# carte_ascenseur_v2.net
KiCad netlist of a schematic drawn in EAGLE
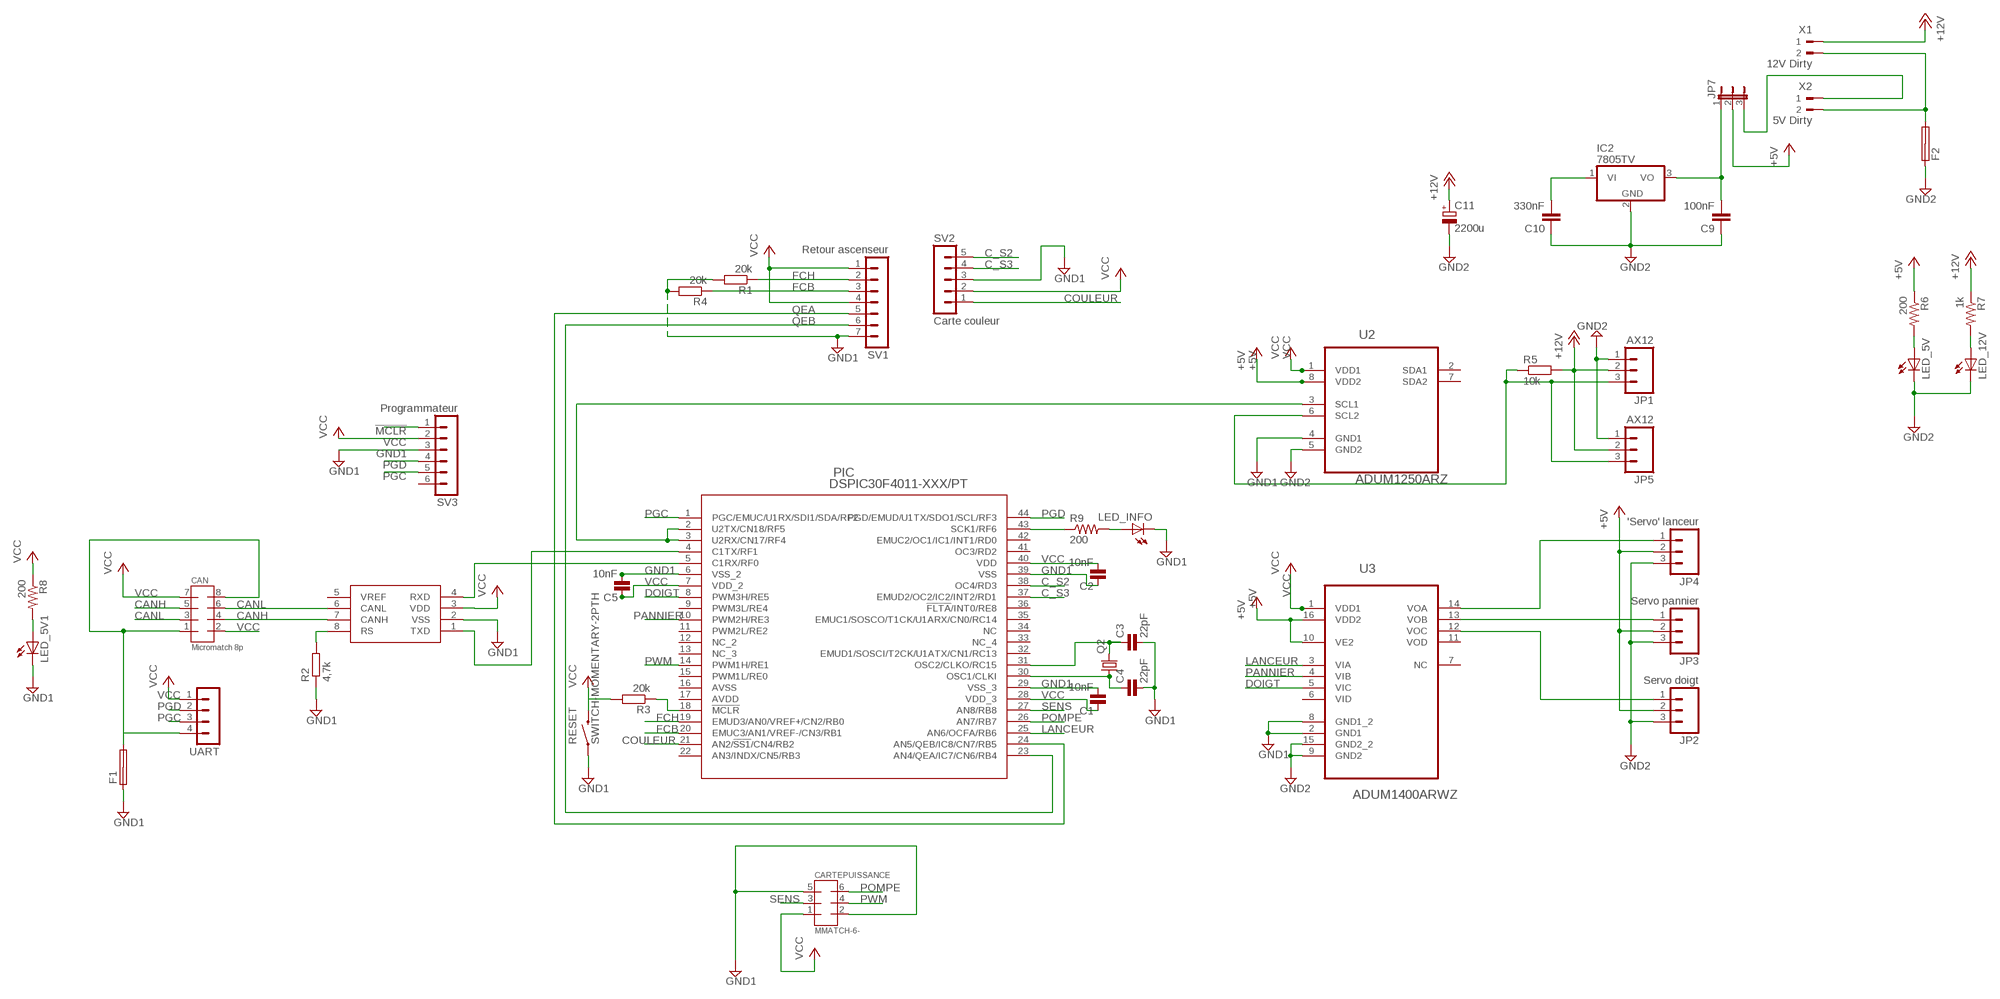
[diagram p0: schematic, sheet 1]

(export (version "E")
  (design (tool "Eeschema 10.0.6"))
  (components
    (comp (ref "C1")
      (value "10nF")
      (footprint "eagle-import:0805")
      (libsource (lib "eagle-import") (part "C0805"))
    )
    (comp (ref "C2")
      (value "10nF")
      (footprint "eagle-import:0805")
      (libsource (lib "eagle-import") (part "C0805"))
    )
    (comp (ref "C3")
      (value "22pF")
      (footprint "eagle-import:0805")
      (libsource (lib "eagle-import") (part "C0805"))
    )
    (comp (ref "C4")
      (value "22pF")
      (footprint "eagle-import:0805")
      (libsource (lib "eagle-import") (part "C0805"))
    )
    (comp (ref "C5")
      (value "10nF")
      (footprint "eagle-import:0805")
      (libsource (lib "eagle-import") (part "C0805"))
    )
    (comp (ref "C9")
      (value "100nF")
      (footprint "eagle-import:C0805")
      (libsource (lib "eagle-import") (part "C-EUC0805"))
    )
    (comp (ref "C10")
      (value "330nF")
      (footprint "eagle-import:C0805")
      (libsource (lib "eagle-import") (part "C-EUC0805"))
    )
    (comp (ref "C11")
      (value "2200u")
      (footprint "eagle-import:TT5D11")
      (libsource (lib "eagle-import") (part "CPOL-EUTT5D11"))
    )
    (comp (ref "CAN")
      (value "Micromatch 8p")
      (footprint "eagle-import:AMP-215079-8")
      (libsource (lib "eagle-import") (part "MMATCH-8-PTH"))
    )
    (comp (ref "CARTEPUISSANCE")
      (value "MMATCH-6-")
      (footprint "eagle-import:AMP-215079-6")
      (libsource (lib "eagle-import") (part "MMATCH-6-"))
    )
    (comp (ref "F1")
      (value "SHK20Q")
      (footprint "eagle-import:SHK20Q")
      (libsource (lib "eagle-import") (part "SHK20Q"))
    )
    (comp (ref "F2")
      (value "SHK20Q")
      (footprint "eagle-import:SHK20Q")
      (libsource (lib "eagle-import") (part "SHK20Q"))
    )
    (comp (ref "IC2")
      (value "7805TV")
      (footprint "eagle-import:TO220V")
      (libsource (lib "eagle-import") (part "78TV05"))
    )
    (comp (ref "JP1")
      (value "AX12")
      (footprint "eagle-import:MOLEX-1X3")
      (libsource (lib "eagle-import") (part "M03POLAR"))
    )
    (comp (ref "JP2")
      (value "Servo doigt")
      (footprint "eagle-import:1X03")
      (libsource (lib "eagle-import") (part "M03PTH"))
    )
    (comp (ref "JP3")
      (value "Servo pannier")
      (footprint "eagle-import:1X03")
      (libsource (lib "eagle-import") (part "M03PTH"))
    )
    (comp (ref "JP4")
      (value "'Servo' lanceur")
      (footprint "eagle-import:1X03")
      (libsource (lib "eagle-import") (part "M03PTH"))
    )
    (comp (ref "JP5")
      (value "AX12")
      (footprint "eagle-import:MOLEX-1X3")
      (libsource (lib "eagle-import") (part "M03POLAR"))
    )
    (comp (ref "JP7")
      (value "JP2E")
      (footprint "eagle-import:JP2")
      (libsource (lib "eagle-import") (part "JP2E"))
    )
    (comp (ref "LED_5V")
      (value "LEDCHIPLED_0805")
      (footprint "eagle-import:CHIPLED_0805")
      (libsource (lib "eagle-import") (part "LEDCHIPLED_0805"))
    )
    (comp (ref "LED_5V1")
      (value "LEDCHIPLED_0805")
      (footprint "eagle-import:CHIPLED_0805")
      (libsource (lib "eagle-import") (part "LEDCHIPLED_0805"))
    )
    (comp (ref "LED_12V")
      (value "LEDCHIPLED_0805")
      (footprint "eagle-import:CHIPLED_0805")
      (libsource (lib "eagle-import") (part "LEDCHIPLED_0805"))
    )
    (comp (ref "LED_INFO")
      (value "LEDCHIPLED_0805")
      (footprint "eagle-import:CHIPLED_0805")
      (libsource (lib "eagle-import") (part "LEDCHIPLED_0805"))
    )
    (comp (ref "PIC")
      (value "DSPIC30F4011-XXX/PT")
      (footprint "eagle-import:TQFP44_MC")
      (libsource (lib "eagle-import") (part "DSPIC30F4011-XXX/PT"))
    )
    (comp (ref "Q2")
      (value "CRYSTALHC49S")
      (footprint "eagle-import:HC49_S")
      (libsource (lib "eagle-import") (part "CRYSTALHC49S"))
    )
    (comp (ref "R1")
      (value "20k")
      (footprint "eagle-import:M0805")
      (libsource (lib "eagle-import") (part "R-EU_M0805"))
    )
    (comp (ref "R2")
      (value "4,7k")
      (footprint "eagle-import:M0805")
      (libsource (lib "eagle-import") (part "R-EU_M0805"))
    )
    (comp (ref "R3")
      (value "20k")
      (footprint "eagle-import:M0805")
      (libsource (lib "eagle-import") (part "R-EU_M0805"))
    )
    (comp (ref "R4")
      (value "20k")
      (footprint "eagle-import:M0805")
      (libsource (lib "eagle-import") (part "R-EU_M0805"))
    )
    (comp (ref "R5")
      (value "10k")
      (footprint "eagle-import:M0805")
      (libsource (lib "eagle-import") (part "R-EU_M0805"))
    )
    (comp (ref "R6")
      (value "200")
      (footprint "eagle-import:0805")
      (libsource (lib "eagle-import") (part "RESISTOR0805-RES"))
    )
    (comp (ref "R7")
      (value "1k")
      (footprint "eagle-import:0805")
      (libsource (lib "eagle-import") (part "RESISTOR0805-RES"))
    )
    (comp (ref "R8")
      (value "200")
      (footprint "eagle-import:0805")
      (libsource (lib "eagle-import") (part "RESISTOR0805-RES"))
    )
    (comp (ref "R9")
      (value "200")
      (footprint "eagle-import:0805")
      (libsource (lib "eagle-import") (part "RESISTOR0805-RES"))
    )
    (comp (ref "RESET")
      (value "SWITCH-MOMENTARY-2PTH")
      (footprint "eagle-import:TACTILE-PTH")
      (libsource (lib "eagle-import") (part "SWITCH-MOMENTARY-2PTH"))
    )
    (comp (ref "SV1")
      (value "Retour ascenseur")
      (footprint "eagle-import:MA07-1")
      (libsource (lib "eagle-import") (part "MA07-1"))
    )
    (comp (ref "SV2")
      (value "Carte couleur")
      (footprint "eagle-import:MA05-1")
      (libsource (lib "eagle-import") (part "MA05-1"))
    )
    (comp (ref "SV3")
      (value "Programmateur")
      (footprint "eagle-import:MA06-1")
      (libsource (lib "eagle-import") (part "MA06-1"))
    )
    (comp (ref "U1")
      (value "MCP2551")
      (footprint "eagle-import:SO08")
      (libsource (lib "eagle-import") (part "MCP2551"))
    )
    (comp (ref "U2")
      (value "ADUM1250ARZ")
      (footprint "eagle-import:SOIC127P600X175-8N")
      (libsource (lib "eagle-import") (part "ADUM1250ARZ"))
    )
    (comp (ref "U3")
      (value "ADUM1400ARWZ")
      (footprint "eagle-import:SOIC127P1032X265-16N")
      (libsource (lib "eagle-import") (part "ADUM1400ARWZ"))
    )
    (comp (ref "UART")
      (value "MA04-1")
      (footprint "eagle-import:MA04-1")
      (libsource (lib "eagle-import") (part "MA04-1"))
    )
    (comp (ref "X1")
      (value "12V Dirty")
      (footprint "eagle-import:90-2")
      (libsource (lib "eagle-import") (part "90-2"))
    )
    (comp (ref "X2")
      (value "5V Dirty")
      (footprint "eagle-import:90-2")
      (fields (field (name "OC_FARNELL") "unknown") (field (name "OC_NEWARK") "unknown"))
      (libsource (lib "eagle-import") (part "90-2"))
    )
  )
  (nets
    (net (code "1") (name "+5V") (class "Default")
      (node (ref "JP2") (pin "2") (pinfunction "2_2") (pintype "passive"))
      (node (ref "JP3") (pin "2") (pinfunction "2_2") (pintype "passive"))
      (node (ref "JP4") (pin "2") (pinfunction "2_2") (pintype "passive"))
      (node (ref "JP7") (pin "2") (pinfunction "2_2") (pintype "passive"))
      (node (ref "R6") (pin "1") (pinfunction "1_1") (pintype "passive"))
      (node (ref "U2") (pin "8") (pinfunction "VDD2_8") (pintype "power_in"))
      (node (ref "U3") (pin "10") (pinfunction "VE2_10") (pintype "input"))
      (node (ref "U3") (pin "16") (pinfunction "VDD2_16") (pintype "power_in"))
    )
    (net (code "2") (name "+12V") (class "Default")
      (node (ref "C11") (pin "+") (pinfunction "+_+") (pintype "passive"))
      (node (ref "JP1") (pin "2") (pinfunction "2_2") (pintype "passive"))
      (node (ref "JP5") (pin "2") (pinfunction "2_2") (pintype "passive"))
      (node (ref "R5") (pin "2") (pinfunction "2_2") (pintype "passive"))
      (node (ref "R7") (pin "1") (pinfunction "1_1") (pintype "passive"))
      (node (ref "X1") (pin "1") (pinfunction "1_1") (pintype "passive"))
    )
    (net (code "3") (name "/CANH") (class "Default")
      (node (ref "CAN") (pin "4") (pinfunction "4_4") (pintype "bidirectional"))
      (node (ref "CAN") (pin "5") (pinfunction "5_5") (pintype "bidirectional"))
      (node (ref "U1") (pin "7") (pinfunction "CANH_7") (pintype "bidirectional"))
    )
    (net (code "4") (name "/CANL") (class "Default")
      (node (ref "CAN") (pin "3") (pinfunction "3_3") (pintype "bidirectional"))
      (node (ref "CAN") (pin "6") (pinfunction "6_6") (pintype "bidirectional"))
      (node (ref "U1") (pin "6") (pinfunction "CANL_6") (pintype "bidirectional"))
    )
    (net (code "5") (name "/COULEUR") (class "Default")
      (node (ref "PIC") (pin "21") (pinfunction "AN2/~{SS1}/CN4/RB2_21") (pintype "passive"))
      (node (ref "SV2") (pin "1") (pinfunction "1_1") (pintype "passive"))
    )
    (net (code "6") (name "/C_S2") (class "Default")
      (node (ref "PIC") (pin "38") (pinfunction "OC4/RD3_38") (pintype "passive"))
      (node (ref "SV2") (pin "5") (pinfunction "5_5") (pintype "passive"))
    )
    (net (code "7") (name "/C_S3") (class "Default")
      (node (ref "PIC") (pin "37") (pinfunction "EMUD2/OC2/IC2/INT2/RD1_37") (pintype "passive"))
      (node (ref "SV2") (pin "4") (pinfunction "4_4") (pintype "passive"))
    )
    (net (code "8") (name "/DOIGT") (class "Default")
      (node (ref "PIC") (pin "8") (pinfunction "PWM3H/RE5_8") (pintype "passive"))
      (node (ref "U3") (pin "5") (pinfunction "VIC_5") (pintype "input"))
    )
    (net (code "9") (name "/FCB") (class "Default")
      (node (ref "PIC") (pin "20") (pinfunction "EMUC3/AN1/VREF-/CN3/RB1_20") (pintype "passive"))
      (node (ref "R4") (pin "1") (pinfunction "1_1") (pintype "passive"))
      (node (ref "SV1") (pin "3") (pinfunction "3_3") (pintype "passive"))
    )
    (net (code "10") (name "/FCH") (class "Default")
      (node (ref "PIC") (pin "19") (pinfunction "EMUD3/AN0/VREF+/CN2/RB0_19") (pintype "passive"))
      (node (ref "R1") (pin "1") (pinfunction "1_1") (pintype "passive"))
      (node (ref "SV1") (pin "2") (pinfunction "2_2") (pintype "passive"))
    )
    (net (code "11") (name "/LANCEUR") (class "Default")
      (node (ref "PIC") (pin "25") (pinfunction "AN6/OCFA/RB6_25") (pintype "passive"))
      (node (ref "U3") (pin "3") (pinfunction "VIA_3") (pintype "input"))
    )
    (net (code "12") (name "/PANNIER") (class "Default")
      (node (ref "PIC") (pin "10") (pinfunction "PWM2H/RE3_10") (pintype "passive"))
      (node (ref "U3") (pin "4") (pinfunction "VIB_4") (pintype "input"))
    )
    (net (code "13") (name "/PGC") (class "Default")
      (node (ref "PIC") (pin "1") (pinfunction "PGC/EMUC/U1RX/SDI1/SDA/RF2_1") (pintype "passive"))
      (node (ref "SV3") (pin "5") (pinfunction "5_5") (pintype "passive"))
      (node (ref "UART") (pin "3") (pinfunction "3_3") (pintype "passive"))
    )
    (net (code "14") (name "/PGD") (class "Default")
      (node (ref "PIC") (pin "44") (pinfunction "PGD/EMUD/U1TX/SDO1/SCL/RF3_44") (pintype "passive"))
      (node (ref "SV3") (pin "4") (pinfunction "4_4") (pintype "passive"))
      (node (ref "UART") (pin "2") (pinfunction "2_2") (pintype "passive"))
    )
    (net (code "15") (name "/POMPE") (class "Default")
      (node (ref "CARTEPUISSANCE") (pin "6") (pinfunction "8_6") (pintype "bidirectional"))
      (node (ref "PIC") (pin "26") (pinfunction "AN7/RB7_26") (pintype "passive"))
    )
    (net (code "16") (name "/PWM") (class "Default")
      (node (ref "CARTEPUISSANCE") (pin "4") (pinfunction "6_4") (pintype "bidirectional"))
      (node (ref "PIC") (pin "14") (pinfunction "PWM1H/RE1_14") (pintype "passive"))
    )
    (net (code "17") (name "/QEA") (class "Default")
      (node (ref "PIC") (pin "24") (pinfunction "AN5/QEB/IC8/CN7/RB5_24") (pintype "passive"))
      (node (ref "SV1") (pin "5") (pinfunction "5_5") (pintype "passive"))
    )
    (net (code "18") (name "/QEB") (class "Default")
      (node (ref "PIC") (pin "23") (pinfunction "AN4/QEA/IC7/CN6/RB4_23") (pintype "passive"))
      (node (ref "SV1") (pin "6") (pinfunction "6_6") (pintype "passive"))
    )
    (net (code "19") (name "/SENS") (class "Default")
      (node (ref "CARTEPUISSANCE") (pin "3") (pinfunction "5_3") (pintype "bidirectional"))
      (node (ref "PIC") (pin "27") (pinfunction "AN8/RB8_27") (pintype "passive"))
    )
    (net (code "20") (name "/~{MCLR}") (class "Default")
      (node (ref "SV3") (pin "1") (pinfunction "1_1") (pintype "passive"))
    )
    (net (code "21") (name "GND1") (class "Default")
      (node (ref "C1") (pin "2") (pinfunction "P$2_2") (pintype "passive"))
      (node (ref "C2") (pin "1") (pinfunction "P$1_1") (pintype "passive"))
      (node (ref "C3") (pin "2") (pinfunction "P$2_2") (pintype "passive"))
      (node (ref "C4") (pin "2") (pinfunction "P$2_2") (pintype "passive"))
      (node (ref "C5") (pin "2") (pinfunction "P$2_2") (pintype "passive"))
      (node (ref "CARTEPUISSANCE") (pin "2") (pinfunction "4_2") (pintype "bidirectional"))
      (node (ref "CARTEPUISSANCE") (pin "5") (pinfunction "7_5") (pintype "bidirectional"))
      (node (ref "F1") (pin "1A") (pinfunction "1A_1A") (pintype "passive"))
      (node (ref "LED_5V1") (pin "C") (pinfunction "C_C") (pintype "passive"))
      (node (ref "LED_INFO") (pin "C") (pinfunction "C_C") (pintype "passive"))
      (node (ref "PIC") (pin "29") (pinfunction "VSS_3_29") (pintype "passive"))
      (node (ref "PIC") (pin "39") (pinfunction "VSS_39") (pintype "passive"))
      (node (ref "PIC") (pin "6") (pinfunction "VSS_2_6") (pintype "passive"))
      (node (ref "R1") (pin "2") (pinfunction "2_2") (pintype "passive"))
      (node (ref "R2") (pin "1") (pinfunction "1_1") (pintype "passive"))
      (node (ref "R4") (pin "2") (pinfunction "2_2") (pintype "passive"))
      (node (ref "RESET") (pin "1") (pinfunction "1_1") (pintype "passive"))
      (node (ref "SV1") (pin "7") (pinfunction "7_7") (pintype "passive"))
      (node (ref "SV2") (pin "3") (pinfunction "3_3") (pintype "passive"))
      (node (ref "SV3") (pin "3") (pinfunction "3_3") (pintype "passive"))
      (node (ref "U1") (pin "2") (pinfunction "VSS_2") (pintype "bidirectional"))
      (node (ref "U2") (pin "4") (pinfunction "GND1_4") (pintype "passive"))
      (node (ref "U3") (pin "2") (pinfunction "GND1_2") (pintype "passive"))
      (node (ref "U3") (pin "8") (pinfunction "GND1_2_8") (pintype "passive"))
    )
    (net (code "22") (name "GND2") (class "Default")
      (node (ref "C10") (pin "1") (pinfunction "1_1") (pintype "passive"))
      (node (ref "C11") (pin "-") (pinfunction "-_-") (pintype "passive"))
      (node (ref "C9") (pin "1") (pinfunction "1_1") (pintype "passive"))
      (node (ref "F2") (pin "1A") (pinfunction "1A_1A") (pintype "passive"))
      (node (ref "IC2") (pin "2") (pinfunction "GND_2") (pintype "passive"))
      (node (ref "JP1") (pin "1") (pinfunction "1_1") (pintype "passive"))
      (node (ref "JP2") (pin "3") (pinfunction "3_3") (pintype "passive"))
      (node (ref "JP3") (pin "3") (pinfunction "3_3") (pintype "passive"))
      (node (ref "JP4") (pin "3") (pinfunction "3_3") (pintype "passive"))
      (node (ref "JP5") (pin "1") (pinfunction "1_1") (pintype "passive"))
      (node (ref "LED_12V") (pin "C") (pinfunction "C_C") (pintype "passive"))
      (node (ref "LED_5V") (pin "C") (pinfunction "C_C") (pintype "passive"))
      (node (ref "U2") (pin "5") (pinfunction "GND2_5") (pintype "passive"))
      (node (ref "U3") (pin "15") (pinfunction "GND2_2_15") (pintype "passive"))
      (node (ref "U3") (pin "9") (pinfunction "GND2_9") (pintype "passive"))
    )
    (net (code "23") (name "Net-(C3-P$1)") (class "Default")
      (node (ref "C3") (pin "1") (pinfunction "P$1_1") (pintype "passive"))
      (node (ref "PIC") (pin "31") (pinfunction "OSC2/CLKO/RC15_31") (pintype "passive"))
      (node (ref "Q2") (pin "2") (pinfunction "2_2") (pintype "passive"))
    )
    (net (code "24") (name "Net-(C4-P$1)") (class "Default")
      (node (ref "C4") (pin "1") (pinfunction "P$1_1") (pintype "passive"))
      (node (ref "PIC") (pin "30") (pinfunction "OSC1/CLKI_30") (pintype "passive"))
      (node (ref "Q2") (pin "1") (pinfunction "1_1") (pintype "passive"))
    )
    (net (code "25") (name "Net-(CAN-Pad1)") (class "Default")
      (node (ref "CAN") (pin "1") (pinfunction "1_1") (pintype "bidirectional"))
      (node (ref "CAN") (pin "8") (pinfunction "8_8") (pintype "bidirectional"))
      (node (ref "F1") (pin "2A") (pinfunction "2A_2A") (pintype "passive"))
      (node (ref "UART") (pin "4") (pinfunction "4_4") (pintype "passive"))
    )
    (net (code "26") (name "Net-(F2-Pad2A)") (class "Default")
      (node (ref "F2") (pin "2A") (pinfunction "2A_2A") (pintype "passive"))
      (node (ref "X1") (pin "2") (pinfunction "2_2") (pintype "passive"))
      (node (ref "X2") (pin "2") (pinfunction "2_2") (pintype "passive"))
    )
    (net (code "27") (name "Net-(IC2-VI)") (class "Default")
      (node (ref "C10") (pin "2") (pinfunction "2_2") (pintype "passive"))
      (node (ref "IC2") (pin "1") (pinfunction "VI_1") (pintype "input"))
    )
    (net (code "28") (name "Net-(IC2-VO)") (class "Default")
      (node (ref "C9") (pin "2") (pinfunction "2_2") (pintype "passive"))
      (node (ref "IC2") (pin "3") (pinfunction "VO_3") (pintype "passive"))
      (node (ref "JP7") (pin "1") (pinfunction "1_1") (pintype "passive"))
    )
    (net (code "29") (name "Net-(JP7-Pad3)") (class "Default")
      (node (ref "JP7") (pin "3") (pinfunction "3_3") (pintype "passive"))
      (node (ref "X2") (pin "1") (pinfunction "1_1") (pintype "passive"))
    )
    (net (code "30") (name "Net-(LED_5V-PadA)") (class "Default")
      (node (ref "LED_5V") (pin "A") (pinfunction "A_A") (pintype "passive"))
      (node (ref "R6") (pin "2") (pinfunction "2_2") (pintype "passive"))
    )
    (net (code "31") (name "Net-(LED_5V1-PadA)") (class "Default")
      (node (ref "LED_5V1") (pin "A") (pinfunction "A_A") (pintype "passive"))
      (node (ref "R8") (pin "2") (pinfunction "2_2") (pintype "passive"))
    )
    (net (code "32") (name "Net-(LED_12V-PadA)") (class "Default")
      (node (ref "LED_12V") (pin "A") (pinfunction "A_A") (pintype "passive"))
      (node (ref "R7") (pin "2") (pinfunction "2_2") (pintype "passive"))
    )
    (net (code "33") (name "Net-(LED_INFO-PadA)") (class "Default")
      (node (ref "LED_INFO") (pin "A") (pinfunction "A_A") (pintype "passive"))
      (node (ref "R9") (pin "2") (pinfunction "2_2") (pintype "passive"))
    )
    (net (code "34") (name "Net-(PIC-C1RX{slash}RF0)") (class "Default")
      (node (ref "PIC") (pin "5") (pinfunction "C1RX/RF0_5") (pintype "passive"))
      (node (ref "U1") (pin "4") (pinfunction "RXD_4") (pintype "bidirectional"))
    )
    (net (code "35") (name "Net-(PIC-C1TX{slash}RF1)") (class "Default")
      (node (ref "PIC") (pin "4") (pinfunction "C1TX/RF1_4") (pintype "passive"))
      (node (ref "U1") (pin "1") (pinfunction "TXD_1") (pintype "bidirectional"))
    )
    (net (code "36") (name "Net-(PIC-SCK1{slash}RF6)") (class "Default")
      (node (ref "PIC") (pin "43") (pinfunction "SCK1/RF6_43") (pintype "passive"))
      (node (ref "R9") (pin "1") (pinfunction "1_1") (pintype "passive"))
    )
    (net (code "37") (name "Net-(PIC-U2RX{slash}CN17{slash}RF4)") (class "Default")
      (node (ref "PIC") (pin "2") (pinfunction "U2TX/CN18/RF5_2") (pintype "passive"))
      (node (ref "PIC") (pin "3") (pinfunction "U2RX/CN17/RF4_3") (pintype "passive"))
      (node (ref "U2") (pin "3") (pinfunction "SCL1_3") (pintype "input"))
    )
    (net (code "38") (name "Net-(PIC-~{MCLR})") (class "Default")
      (node (ref "PIC") (pin "18") (pinfunction "~{MCLR}_18") (pintype "passive"))
      (node (ref "R3") (pin "1") (pinfunction "1_1") (pintype "passive"))
    )
    (net (code "39") (name "Net-(U1-RS)") (class "Default")
      (node (ref "R2") (pin "2") (pinfunction "2_2") (pintype "passive"))
      (node (ref "U1") (pin "8") (pinfunction "RS_8") (pintype "bidirectional"))
    )
    (net (code "40") (name "Net-(U2-SCL2)") (class "Default")
      (node (ref "JP1") (pin "3") (pinfunction "3_3") (pintype "passive"))
      (node (ref "JP5") (pin "3") (pinfunction "3_3") (pintype "passive"))
      (node (ref "R5") (pin "1") (pinfunction "1_1") (pintype "passive"))
      (node (ref "U2") (pin "6") (pinfunction "SCL2_6") (pintype "input"))
    )
    (net (code "41") (name "Net-(U3-VOA)") (class "Default")
      (node (ref "JP4") (pin "1") (pinfunction "1_1") (pintype "passive"))
      (node (ref "U3") (pin "14") (pinfunction "VOA_14") (pintype "output"))
    )
    (net (code "42") (name "Net-(U3-VOB)") (class "Default")
      (node (ref "JP3") (pin "1") (pinfunction "1_1") (pintype "passive"))
      (node (ref "U3") (pin "13") (pinfunction "VOB_13") (pintype "output"))
    )
    (net (code "43") (name "Net-(U3-VOC)") (class "Default")
      (node (ref "JP2") (pin "1") (pinfunction "1_1") (pintype "passive"))
      (node (ref "U3") (pin "12") (pinfunction "VOC_12") (pintype "output"))
    )
    (net (code "44") (name "VCC") (class "Default")
      (node (ref "C1") (pin "1") (pinfunction "P$1_1") (pintype "passive"))
      (node (ref "C2") (pin "2") (pinfunction "P$2_2") (pintype "passive"))
      (node (ref "C5") (pin "1") (pinfunction "P$1_1") (pintype "passive"))
      (node (ref "CAN") (pin "2") (pinfunction "2_2") (pintype "bidirectional"))
      (node (ref "CAN") (pin "7") (pinfunction "7_7") (pintype "bidirectional"))
      (node (ref "CARTEPUISSANCE") (pin "1") (pinfunction "3_1") (pintype "bidirectional"))
      (node (ref "PIC") (pin "28") (pinfunction "VDD_3_28") (pintype "passive"))
      (node (ref "PIC") (pin "40") (pinfunction "VDD_40") (pintype "passive"))
      (node (ref "PIC") (pin "7") (pinfunction "VDD_2_7") (pintype "passive"))
      (node (ref "R3") (pin "2") (pinfunction "2_2") (pintype "passive"))
      (node (ref "R8") (pin "1") (pinfunction "1_1") (pintype "passive"))
      (node (ref "RESET") (pin "3") (pinfunction "2_3") (pintype "passive"))
      (node (ref "SV1") (pin "1") (pinfunction "1_1") (pintype "passive"))
      (node (ref "SV1") (pin "4") (pinfunction "4_4") (pintype "passive"))
      (node (ref "SV2") (pin "2") (pinfunction "2_2") (pintype "passive"))
      (node (ref "SV3") (pin "2") (pinfunction "2_2") (pintype "passive"))
      (node (ref "U1") (pin "3") (pinfunction "VDD_3") (pintype "bidirectional"))
      (node (ref "U2") (pin "1") (pinfunction "VDD1_1") (pintype "power_in"))
      (node (ref "U3") (pin "1") (pinfunction "VDD1_1") (pintype "power_in"))
      (node (ref "UART") (pin "1") (pinfunction "1_1") (pintype "passive"))
    )
    (net (code "45") (name "unconnected-(F1-Pad1B)") (class "Default")
      (node (ref "F1") (pin "1B") (pinfunction "1B_1B") (pintype "passive"))
    )
    (net (code "46") (name "unconnected-(F1-Pad2B)") (class "Default")
      (node (ref "F1") (pin "2B") (pinfunction "2B_2B") (pintype "passive"))
    )
    (net (code "47") (name "unconnected-(F2-Pad1B)") (class "Default")
      (node (ref "F2") (pin "1B") (pinfunction "1B_1B") (pintype "passive"))
    )
    (net (code "48") (name "unconnected-(F2-Pad2B)") (class "Default")
      (node (ref "F2") (pin "2B") (pinfunction "2B_2B") (pintype "passive"))
    )
    (net (code "49") (name "unconnected-(PIC-AN3{slash}INDX{slash}CN5{slash}RB3-Pad22)") (class "Default")
      (node (ref "PIC") (pin "22") (pinfunction "AN3/INDX/CN5/RB3_22") (pintype "passive"))
    )
    (net (code "50") (name "unconnected-(PIC-AVDD-Pad17)") (class "Default")
      (node (ref "PIC") (pin "17") (pinfunction "AVDD_17") (pintype "passive"))
    )
    (net (code "51") (name "unconnected-(PIC-AVSS-Pad16)") (class "Default")
      (node (ref "PIC") (pin "16") (pinfunction "AVSS_16") (pintype "passive"))
    )
    (net (code "52") (name "unconnected-(PIC-EMUC1{slash}SOSCO{slash}T1CK{slash}U1ARX{slash}CN0{slash}RC14-Pad35)") (class "Default")
      (node (ref "PIC") (pin "35") (pinfunction "EMUC1/SOSCO/T1CK/U1ARX/CN0/RC14_35") (pintype "passive"))
    )
    (net (code "53") (name "unconnected-(PIC-EMUC2{slash}OC1{slash}IC1{slash}INT1{slash}RD0-Pad42)") (class "Default")
      (node (ref "PIC") (pin "42") (pinfunction "EMUC2/OC1/IC1/INT1/RD0_42") (pintype "passive"))
    )
    (net (code "54") (name "unconnected-(PIC-EMUD1{slash}SOSCI{slash}T2CK{slash}U1ATX{slash}CN1{slash}RC13-Pad32)") (class "Default")
      (node (ref "PIC") (pin "32") (pinfunction "EMUD1/SOSCI/T2CK/U1ATX/CN1/RC13_32") (pintype "passive"))
    )
    (net (code "55") (name "unconnected-(PIC-NC-Pad34)") (class "Default")
      (node (ref "PIC") (pin "34") (pinfunction "NC_34") (pintype "passive"))
    )
    (net (code "56") (name "unconnected-(PIC-NC_2-Pad12)") (class "Default")
      (node (ref "PIC") (pin "12") (pinfunction "NC_2_12") (pintype "passive"))
    )
    (net (code "57") (name "unconnected-(PIC-NC_3-Pad13)") (class "Default")
      (node (ref "PIC") (pin "13") (pinfunction "NC_3_13") (pintype "passive"))
    )
    (net (code "58") (name "unconnected-(PIC-NC_4-Pad33)") (class "Default")
      (node (ref "PIC") (pin "33") (pinfunction "NC_4_33") (pintype "passive"))
    )
    (net (code "59") (name "unconnected-(PIC-OC3{slash}RD2-Pad41)") (class "Default")
      (node (ref "PIC") (pin "41") (pinfunction "OC3/RD2_41") (pintype "passive"))
    )
    (net (code "60") (name "unconnected-(PIC-PWM1L{slash}RE0-Pad15)") (class "Default")
      (node (ref "PIC") (pin "15") (pinfunction "PWM1L/RE0_15") (pintype "passive"))
    )
    (net (code "61") (name "unconnected-(PIC-PWM2L{slash}RE2-Pad11)") (class "Default")
      (node (ref "PIC") (pin "11") (pinfunction "PWM2L/RE2_11") (pintype "passive"))
    )
    (net (code "62") (name "unconnected-(PIC-PWM3L{slash}RE4-Pad9)") (class "Default")
      (node (ref "PIC") (pin "9") (pinfunction "PWM3L/RE4_9") (pintype "passive"))
    )
    (net (code "63") (name "unconnected-(PIC-~{FLTA}{slash}INT0{slash}RE8-Pad36)") (class "Default")
      (node (ref "PIC") (pin "36") (pinfunction "~{FLTA}/INT0/RE8_36") (pintype "passive"))
    )
    (net (code "64") (name "unconnected-(SV3-Pad6)") (class "Default")
      (node (ref "SV3") (pin "6") (pinfunction "6_6") (pintype "passive"))
    )
    (net (code "65") (name "unconnected-(U1-VREF-Pad5)") (class "Default")
      (node (ref "U1") (pin "5") (pinfunction "VREF_5") (pintype "bidirectional"))
    )
    (net (code "66") (name "unconnected-(U2-SDA1-Pad2)") (class "Default")
      (node (ref "U2") (pin "2") (pinfunction "SDA1_2") (pintype "bidirectional"))
    )
    (net (code "67") (name "unconnected-(U2-SDA2-Pad7)") (class "Default")
      (node (ref "U2") (pin "7") (pinfunction "SDA2_7") (pintype "bidirectional"))
    )
    (net (code "68") (name "unconnected-(U3-NC-Pad7)") (class "Default")
      (node (ref "U3") (pin "7") (pinfunction "NC_7") (pintype "no_connect"))
    )
    (net (code "69") (name "unconnected-(U3-VID-Pad6)") (class "Default")
      (node (ref "U3") (pin "6") (pinfunction "VID_6") (pintype "input"))
    )
    (net (code "70") (name "unconnected-(U3-VOD-Pad11)") (class "Default")
      (node (ref "U3") (pin "11") (pinfunction "VOD_11") (pintype "output"))
    )
  )
)
